# 2DD-17-mk-1_1.net
KiCad netlist of a schematic drawn in EAGLE
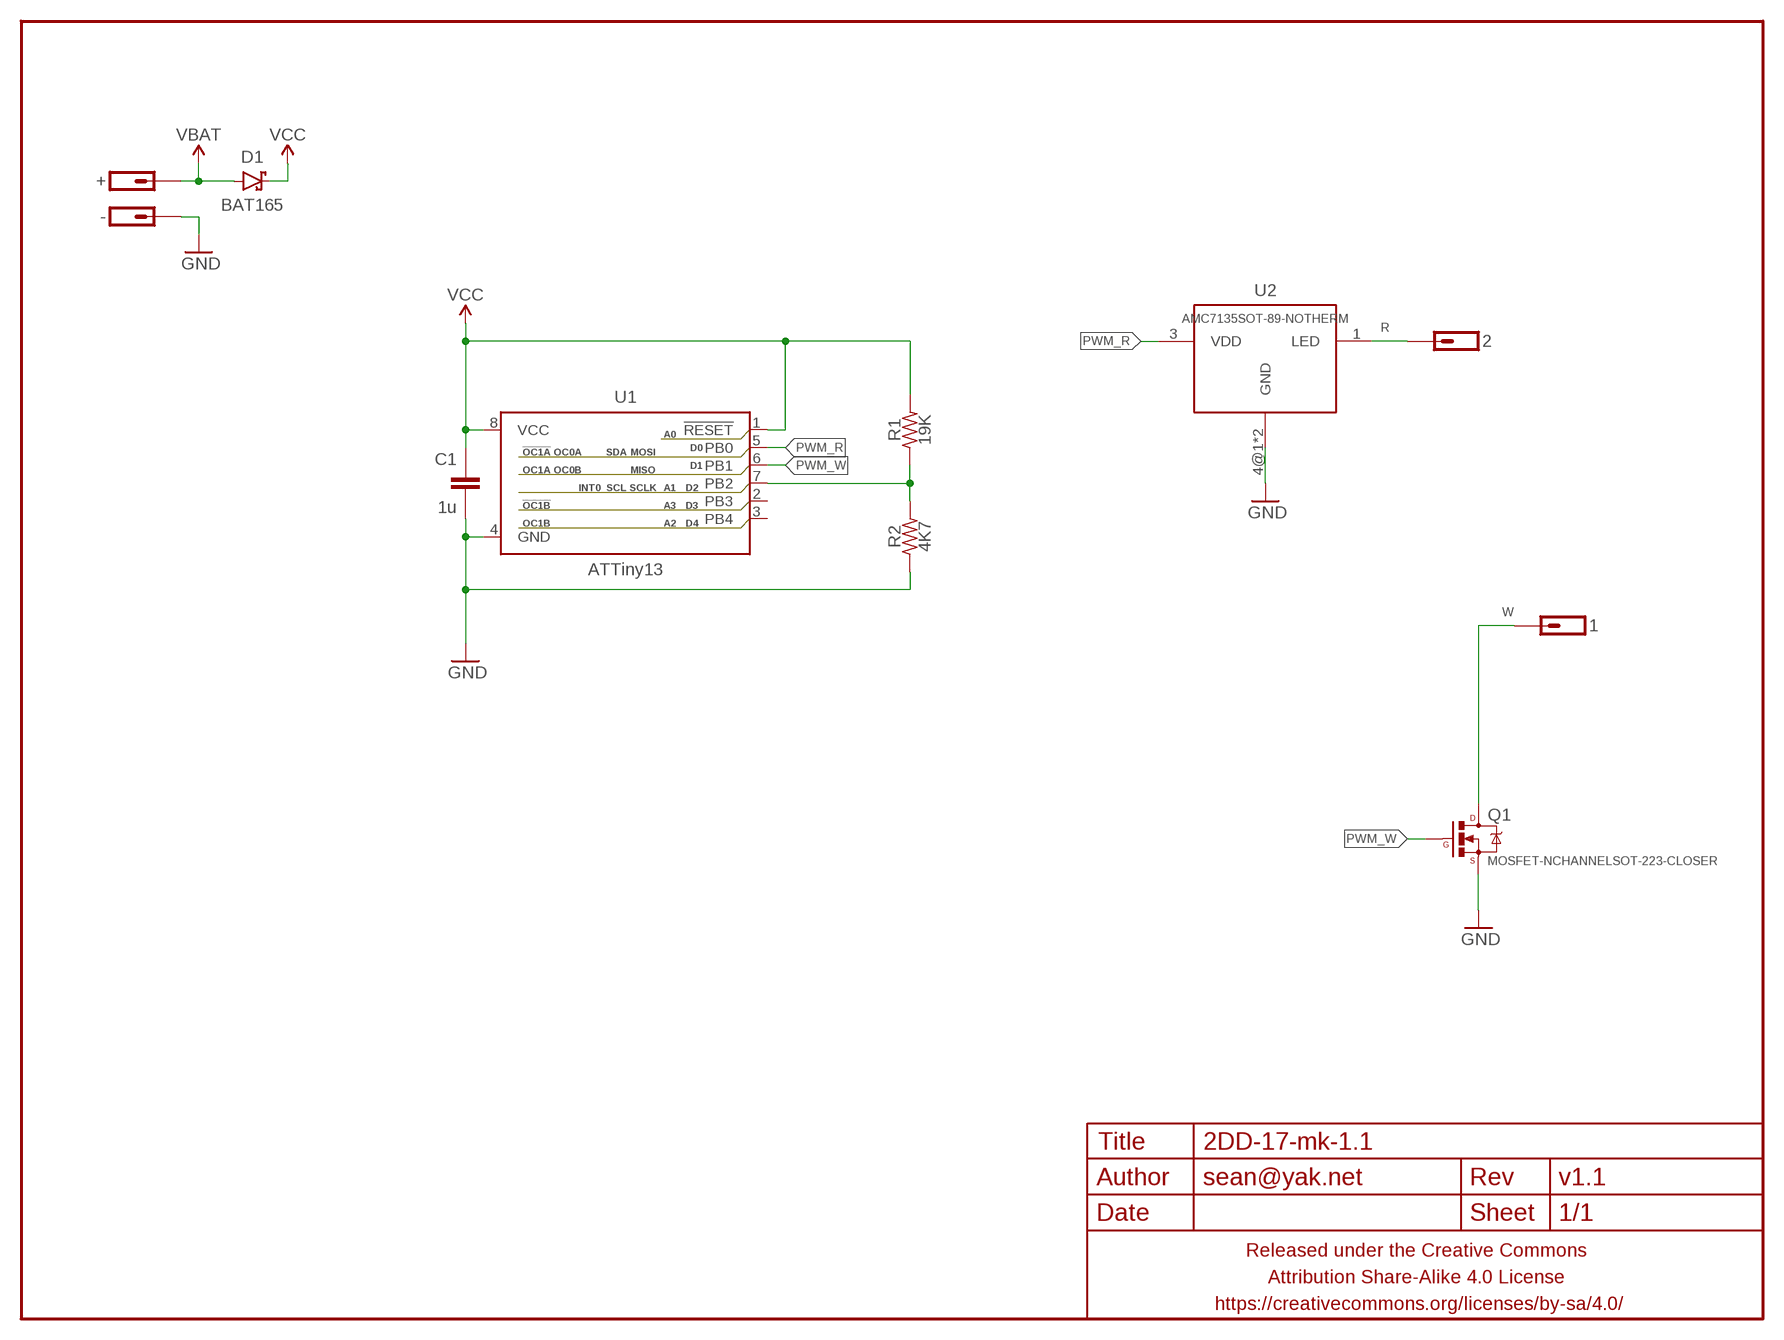
[diagram p0: schematic, sheet 1]

(export (version "E")
  (design (tool "Eeschema 10.0.6"))
  (components
    (comp (ref "+")
      (value "M01PTH-1.2MM-NS")
      (footprint "eagle-import:1X01-1.2MM-NS")
      (libsource (lib "eagle-import") (part "M01PTH-1.2MM-NS"))
    )
    (comp (ref "-")
      (value "M01NOT-A-VIA-NOPE")
      (footprint "eagle-import:1X01_NOSILK_NOSTOP")
      (libsource (lib "eagle-import") (part "M01NOT-A-VIA-NOPE"))
    )
    (comp (ref "1")
      (value "M01SMD-1.25MM-DIA")
      (footprint "eagle-import:1X01-SMD-1.25MM-DIA-NS")
      (libsource (lib "eagle-import") (part "M01SMD-1.25MM-DIA"))
    )
    (comp (ref "2")
      (value "M01SMD-1.25MM-DIA")
      (footprint "eagle-import:1X01-SMD-1.25MM-DIA-NS")
      (libsource (lib "eagle-import") (part "M01SMD-1.25MM-DIA"))
    )
    (comp (ref "C1")
      (value "1u")
      (footprint "eagle-import:C0402")
      (libsource (lib "eagle-import") (part "CAPACITOR-CERAMICC0402"))
    )
    (comp (ref "D1")
      (value "BAT165")
      (footprint "eagle-import:SOD323-SCHOTTKY")
      (libsource (lib "eagle-import") (part "DIODE-SCHOTTKYSOD323"))
    )
    (comp (ref "FRAME1")
      (value "FRAME-LETTERNO_PACKAGE")
      (footprint "eagle-import:DUMMY")
      (fields (field (name "DESIGNER") "sean@yak.net") (field (name "VERSION") "v1.1"))
      (libsource (lib "eagle-import") (part "FRAME-LETTERNO_PACKAGE"))
    )
    (comp (ref "Q1")
      (value "MOSFET-NCHANNELSOT-223-CLOSER")
      (footprint "eagle-import:SOT223-CLOSER")
      (libsource (lib "eagle-import") (part "MOSFET-NCHANNELSOT-223-CLOSER"))
    )
    (comp (ref "R1")
      (value "19K")
      (footprint "eagle-import:R0402")
      (libsource (lib "eagle-import") (part "RESISTORR0402"))
    )
    (comp (ref "R2")
      (value "4K7")
      (footprint "eagle-import:R0402")
      (libsource (lib "eagle-import") (part "RESISTORR0402"))
    )
    (comp (ref "U1")
      (value "ATTiny13")
      (footprint "eagle-import:SO08-NARROWER")
      (libsource (lib "eagle-import") (part "ATTINY13SOIC-NARROWPADS"))
    )
    (comp (ref "U2")
      (value "AMC7135SOT-89-NOTHERM")
      (footprint "eagle-import:SOT89-NOTHERM")
      (libsource (lib "eagle-import") (part "AMC7135SOT-89-NOTHERM"))
    )
  )
  (nets
    (net (code "1") (name "/R") (class "Default")
      (node (ref "2") (pin "P$1") (pinfunction "1_P$1") (pintype "passive"))
      (node (ref "U2") (pin "1") (pinfunction "LED_1") (pintype "bidirectional"))
    )
    (net (code "2") (name "/W") (class "Default")
      (node (ref "1") (pin "P$1") (pinfunction "1_P$1") (pintype "passive"))
      (node (ref "Q1") (pin "2") (pinfunction "D_2") (pintype "passive"))
      (node (ref "Q1") (pin "4") (pinfunction "D_4") (pintype "passive"))
    )
    (net (code "3") (name "GND") (class "Default")
      (node (ref "-") (pin "P$1") (pinfunction "1_P$1") (pintype "passive"))
      (node (ref "C1") (pin "2") (pinfunction "2_2") (pintype "passive"))
      (node (ref "Q1") (pin "3") (pinfunction "S_3") (pintype "passive"))
      (node (ref "R2") (pin "1") (pinfunction "1_1") (pintype "passive"))
      (node (ref "U1") (pin "4") (pinfunction "GND_4") (pintype "bidirectional"))
      (node (ref "U2") (pin "4@1") (pinfunction "GND_4@1") (pintype "bidirectional"))
      (node (ref "U2") (pin "4@2") (pinfunction "GND_4@2") (pintype "bidirectional"))
    )
    (net (code "4") (name "Net-(U1-PB2)") (class "Default")
      (node (ref "R1") (pin "1") (pinfunction "1_1") (pintype "passive"))
      (node (ref "R2") (pin "2") (pinfunction "2_2") (pintype "passive"))
      (node (ref "U1") (pin "7") (pinfunction "PB2_7") (pintype "bidirectional"))
    )
    (net (code "5") (name "PWM_R") (class "Default")
      (node (ref "U1") (pin "5") (pinfunction "PB0_5") (pintype "bidirectional"))
      (node (ref "U2") (pin "3") (pinfunction "VDD_3") (pintype "bidirectional"))
    )
    (net (code "6") (name "PWM_W") (class "Default")
      (node (ref "Q1") (pin "1") (pinfunction "G_1") (pintype "passive"))
      (node (ref "U1") (pin "6") (pinfunction "PB1_6") (pintype "bidirectional"))
    )
    (net (code "7") (name "VBAT") (class "Default")
      (node (ref "+") (pin "P$1") (pinfunction "1_P$1") (pintype "passive"))
      (node (ref "D1") (pin "A") (pinfunction "A_A") (pintype "passive"))
    )
    (net (code "8") (name "VCC") (class "Default")
      (node (ref "C1") (pin "1") (pinfunction "1_1") (pintype "passive"))
      (node (ref "D1") (pin "C") (pinfunction "C_C") (pintype "passive"))
      (node (ref "R1") (pin "2") (pinfunction "2_2") (pintype "passive"))
      (node (ref "U1") (pin "1") (pinfunction "~{RESET}_1") (pintype "bidirectional"))
      (node (ref "U1") (pin "8") (pinfunction "VCC_8") (pintype "bidirectional"))
    )
    (net (code "9") (name "unconnected-(U1-PB3-Pad2)") (class "Default")
      (node (ref "U1") (pin "2") (pinfunction "PB3_2") (pintype "bidirectional"))
    )
    (net (code "10") (name "unconnected-(U1-PB4-Pad3)") (class "Default")
      (node (ref "U1") (pin "3") (pinfunction "PB4_3") (pintype "bidirectional"))
    )
  )
)
